# Connector_Schematic.net
KiCad netlist of a schematic drawn in Altium Designer
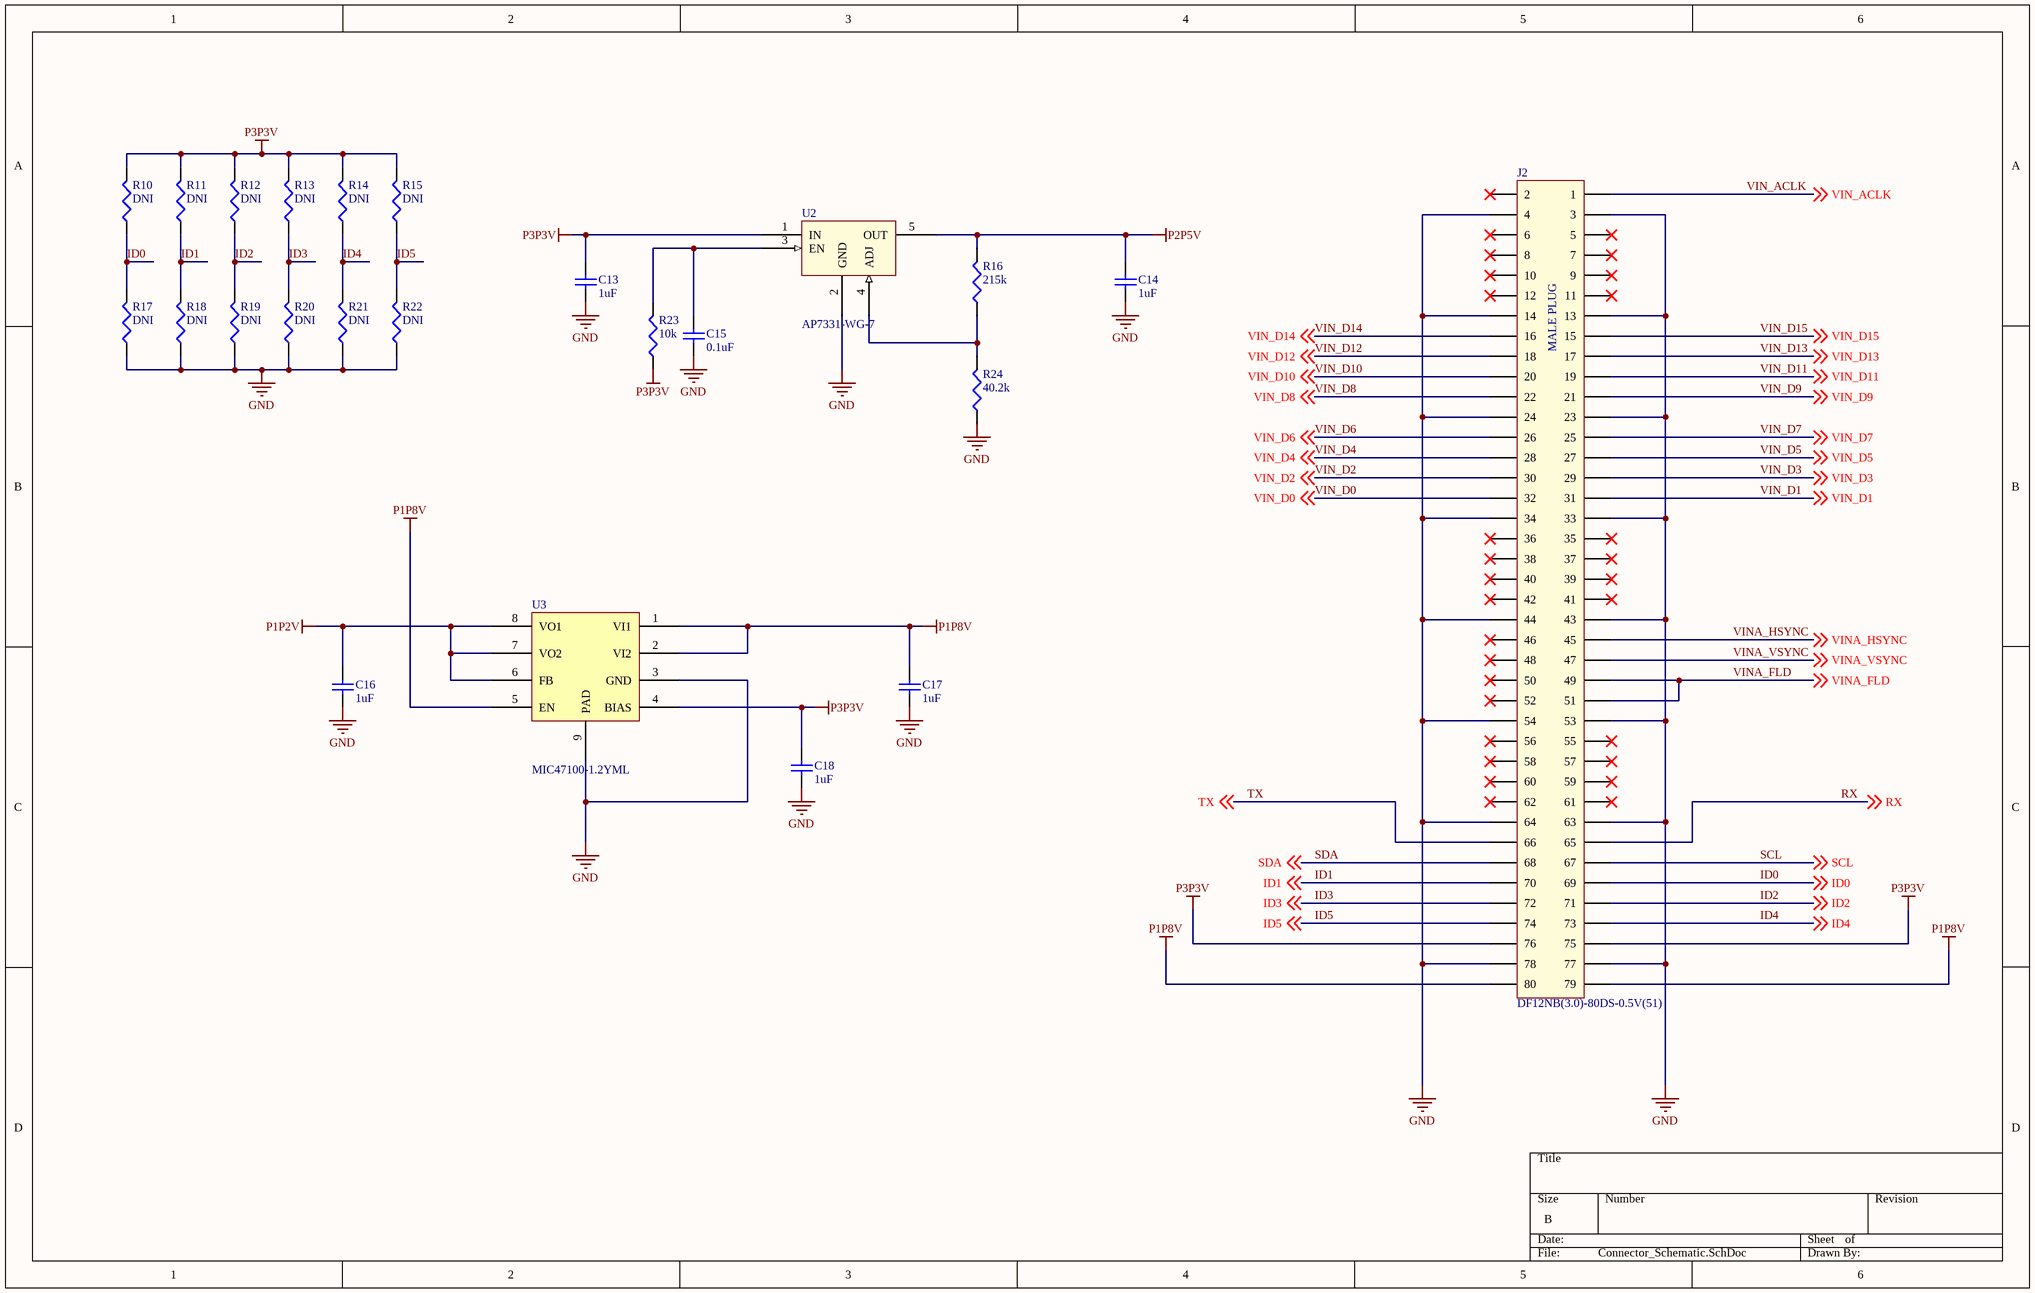
[diagram p0: Connector_Schematic.SchDoc]

(export (version "E")
  (design (tool "Eeschema 10.0.6"))
  (components
    (comp (ref "C13")
      (value "1uF")
      (footprint "CAP_0402_MED")
      (description "CAP CER 1UF 25V X5R 0402")
      (fields (field (name "MFGPARTNO") "EMK105BJ105KV-F") (field (name "MFG") "Taiyo Yuden"))
      (libsource (lib "SLA3000-FPGA[4086]") (part "CMP-00695-A.2"))
    )
    (comp (ref "C14")
      (value "1uF")
      (footprint "CAP_0402_MED")
      (description "CAP CER 1UF 25V X5R 0402")
      (fields (field (name "MFGPARTNO") "EMK105BJ105KV-F") (field (name "MFG") "Taiyo Yuden"))
      (libsource (lib "SLA3000-FPGA[4086]") (part "CMP-00695-A.2"))
    )
    (comp (ref "C15")
      (value "0.1uF")
      (footprint "CAP_0402_MED")
      (description "CAP CER 0.1UF 25V X7R 0402")
      (fields (field (name "SLA PART NO") "SL00150") (field (name "MFG") "TDK"))
      (libsource (lib "SLA3000-FPGA[4086]") (part "CMP-00496-A.6"))
    )
    (comp (ref "C16")
      (value "1uF")
      (footprint "CAP_0402_MED")
      (description "CAP CER 1UF 25V X5R 0402")
      (fields (field (name "MFGPARTNO") "EMK105BJ105KV-F") (field (name "MFG") "Taiyo Yuden"))
      (libsource (lib "SLA3000-FPGA[4086]") (part "CMP-00695-A.2"))
    )
    (comp (ref "C17")
      (value "1uF")
      (footprint "CAP_0402_MED")
      (description "CAP CER 1UF 25V X5R 0402")
      (fields (field (name "MFGPARTNO") "EMK105BJ105KV-F") (field (name "MFG") "Taiyo Yuden"))
      (libsource (lib "SLA3000-FPGA[4086]") (part "CMP-00695-A.2"))
    )
    (comp (ref "C18")
      (value "1uF")
      (footprint "CAP_0402_MED")
      (description "CAP CER 1UF 25V X5R 0402")
      (fields (field (name "MFGPARTNO") "EMK105BJ105KV-F") (field (name "MFG") "Taiyo Yuden"))
      (libsource (lib "SLA3000-FPGA[4086]") (part "CMP-00695-A.2"))
    )
    (comp (ref "J2")
      (value "DF12NB(3.0)-80DS-0.5V(51)")
      (footprint "DF12NB(3.0)-80DS-0.5V(51)")
      (description "DF12NB(3.0)-80DS-0.5V(51) HIROSE CONN HEADER 80POS 3MM SMD 0.5MM")
      (fields (field (name "MFG") "Hirose"))
      (libsource (lib "SLA3000-FPGA[4086]") (part "CMP-00854-A.1"))
    )
    (comp (ref "R10")
      (value "DNI")
      (footprint "RES_0402_MED")
      (description "Do Not Populate 0402 Res")
      (libsource (lib "SLA3000-FPGA[4086]") (part "CMP-00432-A.10"))
    )
    (comp (ref "R11")
      (value "DNI")
      (footprint "RES_0402_MED")
      (description "Do Not Populate 0402 Res")
      (libsource (lib "SLA3000-FPGA[4086]") (part "CMP-00432-A.10"))
    )
    (comp (ref "R12")
      (value "DNI")
      (footprint "RES_0402_MED")
      (description "Do Not Populate 0402 Res")
      (libsource (lib "SLA3000-FPGA[4086]") (part "CMP-00432-A.10"))
    )
    (comp (ref "R13")
      (value "DNI")
      (footprint "RES_0402_MED")
      (description "Do Not Populate 0402 Res")
      (libsource (lib "SLA3000-FPGA[4086]") (part "CMP-00432-A.10"))
    )
    (comp (ref "R14")
      (value "DNI")
      (footprint "RES_0402_MED")
      (description "Do Not Populate 0402 Res")
      (libsource (lib "SLA3000-FPGA[4086]") (part "CMP-00432-A.10"))
    )
    (comp (ref "R15")
      (value "DNI")
      (footprint "RES_0402_MED")
      (description "Do Not Populate 0402 Res")
      (libsource (lib "SLA3000-FPGA[4086]") (part "CMP-00432-A.10"))
    )
    (comp (ref "R16")
      (value "215k")
      (footprint "RES_0402_MED")
      (description "RES SMD 215K OHM 1% 1/16W 0402")
      (fields (field (name "MFGPARTNO") "RC0402FR-07215KL") (field (name "MFG") "Yageo"))
      (libsource (lib "SLA3000-FPGA[4086]") (part "CMP-00638-A.1"))
    )
    (comp (ref "R17")
      (value "DNI")
      (footprint "RES_0402_MED")
      (description "Do Not Populate 0402 Res")
      (libsource (lib "SLA3000-FPGA[4086]") (part "CMP-00432-A.10"))
    )
    (comp (ref "R18")
      (value "DNI")
      (footprint "RES_0402_MED")
      (description "Do Not Populate 0402 Res")
      (libsource (lib "SLA3000-FPGA[4086]") (part "CMP-00432-A.10"))
    )
    (comp (ref "R19")
      (value "DNI")
      (footprint "RES_0402_MED")
      (description "Do Not Populate 0402 Res")
      (libsource (lib "SLA3000-FPGA[4086]") (part "CMP-00432-A.10"))
    )
    (comp (ref "R20")
      (value "DNI")
      (footprint "RES_0402_MED")
      (description "Do Not Populate 0402 Res")
      (libsource (lib "SLA3000-FPGA[4086]") (part "CMP-00432-A.10"))
    )
    (comp (ref "R21")
      (value "DNI")
      (footprint "RES_0402_MED")
      (description "Do Not Populate 0402 Res")
      (libsource (lib "SLA3000-FPGA[4086]") (part "CMP-00432-A.10"))
    )
    (comp (ref "R22")
      (value "DNI")
      (footprint "RES_0402_MED")
      (description "Do Not Populate 0402 Res")
      (libsource (lib "SLA3000-FPGA[4086]") (part "CMP-00432-A.10"))
    )
    (comp (ref "R23")
      (value "10k")
      (footprint "RES_0402_MED")
      (description "RES SMD 10K OHM 1% 1/10W 0402")
      (fields (field (name "SLA PART NO") "SL00225") (field (name "MFG") "Panasonic"))
      (libsource (lib "SLA3000-FPGA[4086]") (part "CMP-00396-A.9"))
    )
    (comp (ref "R24")
      (value "40.2k")
      (footprint "RES_0402_MED")
      (description "RES 40.2K OHM 1/10W 1% 0402 SMD")
      (fields (field (name "SLA PART NO") "SL00235") (field (name "MFGPARTNO") "ERJ-2RKF4022X"))
      (libsource (lib "SLA3000-FPGA[4086]") (part "CMP-00410-A.9"))
    )
    (comp (ref "U2")
      (value "AP7331-WG-7")
      (footprint "SOT25-3 (for AP7331-WG-7)")
      (description "Adj 0.8-5V Out, 2-6V In, 300mA, AP7331-WG-7 LDO SOT23-5")
      (fields (field (name "SLA PART NO") "SL00740") (field (name "MFG") "Diodes Inc."))
      (libsource (lib "SLA3000-FPGA[4086]") (part "CMP-00547-A.3"))
    )
    (comp (ref "U3")
      (value "MIC47100-1.2YML")
      (footprint "MLF2x2")
      (description "1.2V, 1A, MIC47100-1.2TML IC REG LDO 8MLF")
      (fields (field (name "MFG") "Micrel") (field (name "SLA PART NO") "SL00247"))
      (libsource (lib "SLA3000-FPGA[4086]") (part "CMP-00239-A.3"))
    )
  )
  (nets
    (net (code "1") (name "GND") (class "Default")
      (node (ref "C13") (pin "1") (pinfunction "1_1") (pintype "passive"))
      (node (ref "C14") (pin "1") (pinfunction "1_1") (pintype "passive"))
      (node (ref "C15") (pin "1") (pinfunction "1_1") (pintype "passive"))
      (node (ref "C16") (pin "1") (pinfunction "1_1") (pintype "passive"))
      (node (ref "C17") (pin "1") (pinfunction "1_1") (pintype "passive"))
      (node (ref "C18") (pin "1") (pinfunction "1_1") (pintype "passive"))
      (node (ref "J2") (pin "13") (pinfunction "13_13") (pintype "passive"))
      (node (ref "J2") (pin "14") (pinfunction "14_14") (pintype "passive"))
      (node (ref "J2") (pin "23") (pinfunction "23_23") (pintype "passive"))
      (node (ref "J2") (pin "24") (pinfunction "24_24") (pintype "passive"))
      (node (ref "J2") (pin "3") (pinfunction "3_3") (pintype "passive"))
      (node (ref "J2") (pin "33") (pinfunction "33_33") (pintype "passive"))
      (node (ref "J2") (pin "34") (pinfunction "34_34") (pintype "passive"))
      (node (ref "J2") (pin "4") (pinfunction "4_4") (pintype "passive"))
      (node (ref "J2") (pin "43") (pinfunction "43_43") (pintype "passive"))
      (node (ref "J2") (pin "44") (pinfunction "44_44") (pintype "passive"))
      (node (ref "J2") (pin "53") (pinfunction "53_53") (pintype "passive"))
      (node (ref "J2") (pin "54") (pinfunction "54_54") (pintype "passive"))
      (node (ref "J2") (pin "63") (pinfunction "63_63") (pintype "passive"))
      (node (ref "J2") (pin "64") (pinfunction "64_64") (pintype "passive"))
      (node (ref "J2") (pin "77") (pinfunction "77_77") (pintype "passive"))
      (node (ref "J2") (pin "78") (pinfunction "78_78") (pintype "passive"))
      (node (ref "R17") (pin "1") (pinfunction "1_1") (pintype "passive"))
      (node (ref "R18") (pin "1") (pinfunction "1_1") (pintype "passive"))
      (node (ref "R19") (pin "1") (pinfunction "1_1") (pintype "passive"))
      (node (ref "R20") (pin "1") (pinfunction "1_1") (pintype "passive"))
      (node (ref "R21") (pin "1") (pinfunction "1_1") (pintype "passive"))
      (node (ref "R22") (pin "1") (pinfunction "1_1") (pintype "passive"))
      (node (ref "R24") (pin "1") (pinfunction "1_1") (pintype "passive"))
      (node (ref "U2") (pin "2") (pinfunction "GND_2") (pintype "power_in"))
      (node (ref "U3") (pin "3") (pinfunction "GND_3") (pintype "passive"))
      (node (ref "U3") (pin "9") (pinfunction "PAD_9") (pintype "passive"))
    )
    (net (code "2") (name "ID0") (class "Default")
      (node (ref "J2") (pin "69") (pinfunction "69_69") (pintype "passive"))
      (node (ref "R10") (pin "1") (pinfunction "1_1") (pintype "passive"))
      (node (ref "R17") (pin "2") (pinfunction "2_2") (pintype "passive"))
    )
    (net (code "3") (name "ID1") (class "Default")
      (node (ref "J2") (pin "70") (pinfunction "70_70") (pintype "passive"))
      (node (ref "R11") (pin "1") (pinfunction "1_1") (pintype "passive"))
      (node (ref "R18") (pin "2") (pinfunction "2_2") (pintype "passive"))
    )
    (net (code "4") (name "ID2") (class "Default")
      (node (ref "J2") (pin "71") (pinfunction "71_71") (pintype "passive"))
      (node (ref "R12") (pin "1") (pinfunction "1_1") (pintype "passive"))
      (node (ref "R19") (pin "2") (pinfunction "2_2") (pintype "passive"))
    )
    (net (code "5") (name "ID3") (class "Default")
      (node (ref "J2") (pin "72") (pinfunction "72_72") (pintype "passive"))
      (node (ref "R13") (pin "1") (pinfunction "1_1") (pintype "passive"))
      (node (ref "R20") (pin "2") (pinfunction "2_2") (pintype "passive"))
    )
    (net (code "6") (name "ID4") (class "Default")
      (node (ref "J2") (pin "73") (pinfunction "73_73") (pintype "passive"))
      (node (ref "R14") (pin "1") (pinfunction "1_1") (pintype "passive"))
      (node (ref "R21") (pin "2") (pinfunction "2_2") (pintype "passive"))
    )
    (net (code "7") (name "ID5") (class "Default")
      (node (ref "J2") (pin "74") (pinfunction "74_74") (pintype "passive"))
      (node (ref "R15") (pin "1") (pinfunction "1_1") (pintype "passive"))
      (node (ref "R22") (pin "2") (pinfunction "2_2") (pintype "passive"))
    )
    (net (code "8") (name "Net-(U2-ADJ)") (class "Default")
      (node (ref "R16") (pin "1") (pinfunction "1_1") (pintype "passive"))
      (node (ref "R24") (pin "2") (pinfunction "2_2") (pintype "passive"))
      (node (ref "U2") (pin "4") (pinfunction "ADJ_4") (pintype "input"))
    )
    (net (code "9") (name "Net-(U2-EN)") (class "Default")
      (node (ref "C15") (pin "2") (pinfunction "2_2") (pintype "passive"))
      (node (ref "R23") (pin "2") (pinfunction "2_2") (pintype "passive"))
      (node (ref "U2") (pin "3") (pinfunction "EN_3") (pintype "input"))
    )
    (net (code "10") (name "P1P2V") (class "Default")
      (node (ref "C16") (pin "2") (pinfunction "2_2") (pintype "passive"))
      (node (ref "U3") (pin "6") (pinfunction "FB_6") (pintype "passive"))
      (node (ref "U3") (pin "7") (pinfunction "VO2_7") (pintype "passive"))
      (node (ref "U3") (pin "8") (pinfunction "VO1_8") (pintype "passive"))
    )
    (net (code "11") (name "P1P8V") (class "Default")
      (node (ref "C17") (pin "2") (pinfunction "2_2") (pintype "passive"))
      (node (ref "J2") (pin "79") (pinfunction "79_79") (pintype "passive"))
      (node (ref "J2") (pin "80") (pinfunction "80_80") (pintype "passive"))
      (node (ref "U3") (pin "1") (pinfunction "VI1_1") (pintype "passive"))
      (node (ref "U3") (pin "2") (pinfunction "VI2_2") (pintype "passive"))
      (node (ref "U3") (pin "5") (pinfunction "EN_5") (pintype "passive"))
    )
    (net (code "12") (name "P2P5V") (class "Default")
      (node (ref "C14") (pin "2") (pinfunction "2_2") (pintype "passive"))
      (node (ref "R16") (pin "2") (pinfunction "2_2") (pintype "passive"))
      (node (ref "U2") (pin "5") (pinfunction "OUT_5") (pintype "power_in"))
    )
    (net (code "13") (name "P3P3V") (class "Default")
      (node (ref "C13") (pin "2") (pinfunction "2_2") (pintype "passive"))
      (node (ref "C18") (pin "2") (pinfunction "2_2") (pintype "passive"))
      (node (ref "J2") (pin "75") (pinfunction "75_75") (pintype "passive"))
      (node (ref "J2") (pin "76") (pinfunction "76_76") (pintype "passive"))
      (node (ref "R10") (pin "2") (pinfunction "2_2") (pintype "passive"))
      (node (ref "R11") (pin "2") (pinfunction "2_2") (pintype "passive"))
      (node (ref "R12") (pin "2") (pinfunction "2_2") (pintype "passive"))
      (node (ref "R13") (pin "2") (pinfunction "2_2") (pintype "passive"))
      (node (ref "R14") (pin "2") (pinfunction "2_2") (pintype "passive"))
      (node (ref "R15") (pin "2") (pinfunction "2_2") (pintype "passive"))
      (node (ref "R23") (pin "1") (pinfunction "1_1") (pintype "passive"))
      (node (ref "U2") (pin "1") (pinfunction "IN_1") (pintype "power_in"))
      (node (ref "U3") (pin "4") (pinfunction "BIAS_4") (pintype "passive"))
    )
    (net (code "14") (name "RX") (class "Default")
      (node (ref "J2") (pin "65") (pinfunction "65_65") (pintype "passive"))
    )
    (net (code "15") (name "SCL") (class "Default")
      (node (ref "J2") (pin "67") (pinfunction "67_67") (pintype "passive"))
    )
    (net (code "16") (name "SDA") (class "Default")
      (node (ref "J2") (pin "68") (pinfunction "68_68") (pintype "passive"))
    )
    (net (code "17") (name "TX") (class "Default")
      (node (ref "J2") (pin "66") (pinfunction "66_66") (pintype "passive"))
    )
    (net (code "18") (name "VINA_FLD") (class "Default")
      (node (ref "J2") (pin "49") (pinfunction "49_49") (pintype "passive"))
      (node (ref "J2") (pin "51") (pinfunction "51_51") (pintype "passive"))
    )
    (net (code "19") (name "VINA_HSYNC") (class "Default")
      (node (ref "J2") (pin "45") (pinfunction "45_45") (pintype "passive"))
    )
    (net (code "20") (name "VINA_VSYNC") (class "Default")
      (node (ref "J2") (pin "47") (pinfunction "47_47") (pintype "passive"))
    )
    (net (code "21") (name "VIN_ACLK") (class "Default")
      (node (ref "J2") (pin "1") (pinfunction "1_1") (pintype "passive"))
    )
    (net (code "22") (name "VIN_D0") (class "Default")
      (node (ref "J2") (pin "32") (pinfunction "32_32") (pintype "passive"))
    )
    (net (code "23") (name "VIN_D1") (class "Default")
      (node (ref "J2") (pin "31") (pinfunction "31_31") (pintype "passive"))
    )
    (net (code "24") (name "VIN_D2") (class "Default")
      (node (ref "J2") (pin "30") (pinfunction "30_30") (pintype "passive"))
    )
    (net (code "25") (name "VIN_D3") (class "Default")
      (node (ref "J2") (pin "29") (pinfunction "29_29") (pintype "passive"))
    )
    (net (code "26") (name "VIN_D4") (class "Default")
      (node (ref "J2") (pin "28") (pinfunction "28_28") (pintype "passive"))
    )
    (net (code "27") (name "VIN_D5") (class "Default")
      (node (ref "J2") (pin "27") (pinfunction "27_27") (pintype "passive"))
    )
    (net (code "28") (name "VIN_D6") (class "Default")
      (node (ref "J2") (pin "26") (pinfunction "26_26") (pintype "passive"))
    )
    (net (code "29") (name "VIN_D7") (class "Default")
      (node (ref "J2") (pin "25") (pinfunction "25_25") (pintype "passive"))
    )
    (net (code "30") (name "VIN_D8") (class "Default")
      (node (ref "J2") (pin "22") (pinfunction "22_22") (pintype "passive"))
    )
    (net (code "31") (name "VIN_D9") (class "Default")
      (node (ref "J2") (pin "21") (pinfunction "21_21") (pintype "passive"))
    )
    (net (code "32") (name "VIN_D10") (class "Default")
      (node (ref "J2") (pin "20") (pinfunction "20_20") (pintype "passive"))
    )
    (net (code "33") (name "VIN_D11") (class "Default")
      (node (ref "J2") (pin "19") (pinfunction "19_19") (pintype "passive"))
    )
    (net (code "34") (name "VIN_D12") (class "Default")
      (node (ref "J2") (pin "18") (pinfunction "18_18") (pintype "passive"))
    )
    (net (code "35") (name "VIN_D13") (class "Default")
      (node (ref "J2") (pin "17") (pinfunction "17_17") (pintype "passive"))
    )
    (net (code "36") (name "VIN_D14") (class "Default")
      (node (ref "J2") (pin "16") (pinfunction "16_16") (pintype "passive"))
    )
    (net (code "37") (name "VIN_D15") (class "Default")
      (node (ref "J2") (pin "15") (pinfunction "15_15") (pintype "passive"))
    )
    (net (code "38") (name "unconnected-(J2-Pad2)") (class "Default")
      (node (ref "J2") (pin "2") (pinfunction "2_2") (pintype "passive+no_connect"))
    )
    (net (code "39") (name "unconnected-(J2-Pad5)") (class "Default")
      (node (ref "J2") (pin "5") (pinfunction "5_5") (pintype "passive+no_connect"))
    )
    (net (code "40") (name "unconnected-(J2-Pad6)") (class "Default")
      (node (ref "J2") (pin "6") (pinfunction "6_6") (pintype "passive+no_connect"))
    )
    (net (code "41") (name "unconnected-(J2-Pad7)") (class "Default")
      (node (ref "J2") (pin "7") (pinfunction "7_7") (pintype "passive+no_connect"))
    )
    (net (code "42") (name "unconnected-(J2-Pad8)") (class "Default")
      (node (ref "J2") (pin "8") (pinfunction "8_8") (pintype "passive+no_connect"))
    )
    (net (code "43") (name "unconnected-(J2-Pad9)") (class "Default")
      (node (ref "J2") (pin "9") (pinfunction "9_9") (pintype "passive+no_connect"))
    )
    (net (code "44") (name "unconnected-(J2-Pad10)") (class "Default")
      (node (ref "J2") (pin "10") (pinfunction "10_10") (pintype "passive+no_connect"))
    )
    (net (code "45") (name "unconnected-(J2-Pad11)") (class "Default")
      (node (ref "J2") (pin "11") (pinfunction "11_11") (pintype "passive+no_connect"))
    )
    (net (code "46") (name "unconnected-(J2-Pad12)") (class "Default")
      (node (ref "J2") (pin "12") (pinfunction "12_12") (pintype "passive+no_connect"))
    )
    (net (code "47") (name "unconnected-(J2-Pad35)") (class "Default")
      (node (ref "J2") (pin "35") (pinfunction "35_35") (pintype "passive+no_connect"))
    )
    (net (code "48") (name "unconnected-(J2-Pad36)") (class "Default")
      (node (ref "J2") (pin "36") (pinfunction "36_36") (pintype "passive+no_connect"))
    )
    (net (code "49") (name "unconnected-(J2-Pad37)") (class "Default")
      (node (ref "J2") (pin "37") (pinfunction "37_37") (pintype "passive+no_connect"))
    )
    (net (code "50") (name "unconnected-(J2-Pad38)") (class "Default")
      (node (ref "J2") (pin "38") (pinfunction "38_38") (pintype "passive+no_connect"))
    )
    (net (code "51") (name "unconnected-(J2-Pad39)") (class "Default")
      (node (ref "J2") (pin "39") (pinfunction "39_39") (pintype "passive+no_connect"))
    )
    (net (code "52") (name "unconnected-(J2-Pad40)") (class "Default")
      (node (ref "J2") (pin "40") (pinfunction "40_40") (pintype "passive+no_connect"))
    )
    (net (code "53") (name "unconnected-(J2-Pad41)") (class "Default")
      (node (ref "J2") (pin "41") (pinfunction "41_41") (pintype "passive+no_connect"))
    )
    (net (code "54") (name "unconnected-(J2-Pad42)") (class "Default")
      (node (ref "J2") (pin "42") (pinfunction "42_42") (pintype "passive+no_connect"))
    )
    (net (code "55") (name "unconnected-(J2-Pad46)") (class "Default")
      (node (ref "J2") (pin "46") (pinfunction "46_46") (pintype "passive+no_connect"))
    )
    (net (code "56") (name "unconnected-(J2-Pad48)") (class "Default")
      (node (ref "J2") (pin "48") (pinfunction "48_48") (pintype "passive+no_connect"))
    )
    (net (code "57") (name "unconnected-(J2-Pad50)") (class "Default")
      (node (ref "J2") (pin "50") (pinfunction "50_50") (pintype "passive+no_connect"))
    )
    (net (code "58") (name "unconnected-(J2-Pad52)") (class "Default")
      (node (ref "J2") (pin "52") (pinfunction "52_52") (pintype "passive+no_connect"))
    )
    (net (code "59") (name "unconnected-(J2-Pad55)") (class "Default")
      (node (ref "J2") (pin "55") (pinfunction "55_55") (pintype "passive+no_connect"))
    )
    (net (code "60") (name "unconnected-(J2-Pad56)") (class "Default")
      (node (ref "J2") (pin "56") (pinfunction "56_56") (pintype "passive+no_connect"))
    )
    (net (code "61") (name "unconnected-(J2-Pad57)") (class "Default")
      (node (ref "J2") (pin "57") (pinfunction "57_57") (pintype "passive+no_connect"))
    )
    (net (code "62") (name "unconnected-(J2-Pad58)") (class "Default")
      (node (ref "J2") (pin "58") (pinfunction "58_58") (pintype "passive+no_connect"))
    )
    (net (code "63") (name "unconnected-(J2-Pad59)") (class "Default")
      (node (ref "J2") (pin "59") (pinfunction "59_59") (pintype "passive+no_connect"))
    )
    (net (code "64") (name "unconnected-(J2-Pad60)") (class "Default")
      (node (ref "J2") (pin "60") (pinfunction "60_60") (pintype "passive+no_connect"))
    )
    (net (code "65") (name "unconnected-(J2-Pad61)") (class "Default")
      (node (ref "J2") (pin "61") (pinfunction "61_61") (pintype "passive+no_connect"))
    )
    (net (code "66") (name "unconnected-(J2-Pad62)") (class "Default")
      (node (ref "J2") (pin "62") (pinfunction "62_62") (pintype "passive+no_connect"))
    )
  )
)
